# sch_USB3_0.net
KiCad netlist of a schematic drawn in Altium Designer
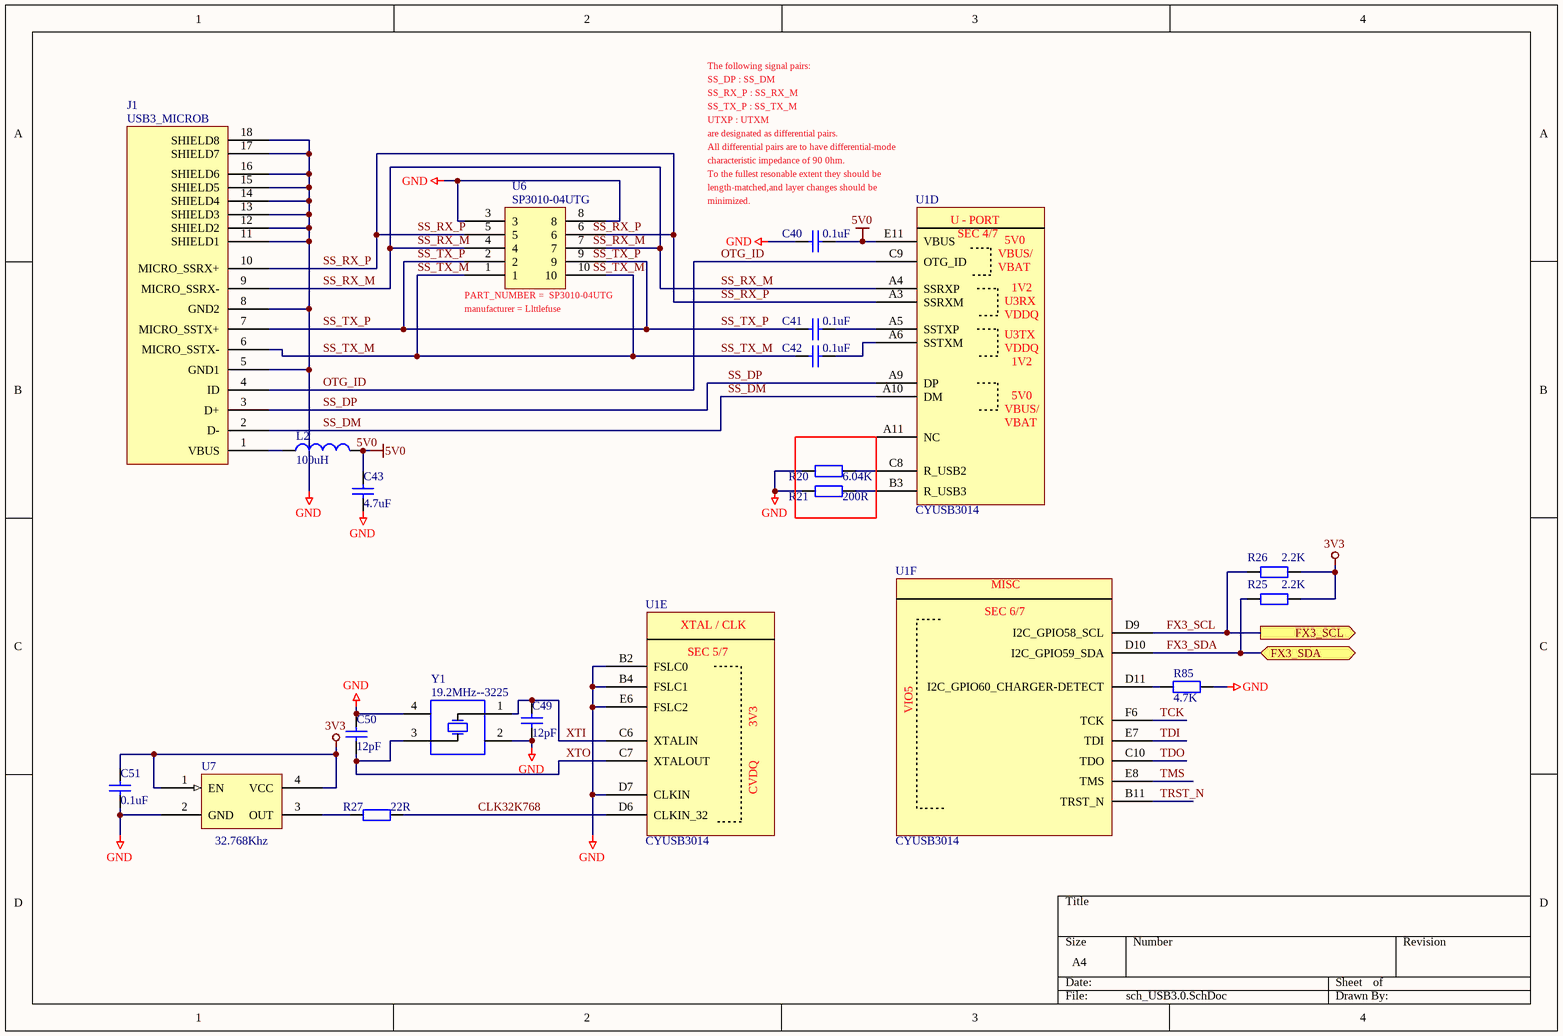
[diagram p0: sch_USB3.0.SchDoc]

(export (version "E")
  (design (tool "Eeschema 10.0.6"))
  (components
    (comp (ref "C40")
      (value "0.1uF")
      (footprint "0402C")
      (description "Capacitor")
      (fields (field (name "PUBLISHER") "Altium Limited"))
      (libsource (lib "Miscellaneous Devices") (part "Cap"))
    )
    (comp (ref "C41")
      (value "0.1uF")
      (footprint "0402C")
      (description "Capacitor")
      (fields (field (name "PUBLISHER") "Altium Limited"))
      (libsource (lib "Miscellaneous Devices") (part "Cap"))
    )
    (comp (ref "C42")
      (value "0.1uF")
      (footprint "0402C")
      (description "Capacitor")
      (fields (field (name "PUBLISHER") "Altium Limited"))
      (libsource (lib "Miscellaneous Devices") (part "Cap"))
    )
    (comp (ref "C43")
      (value "4.7uF")
      (description "Capacitor")
      (fields (field (name "PUBLISHER") "Altium Limited"))
      (libsource (lib "Miscellaneous Devices") (part "Cap"))
    )
    (comp (ref "C49")
      (value "12pF")
      (footprint "0402C")
      (description "Capacitor")
      (fields (field (name "PUBLISHER") "Altium Limited"))
      (libsource (lib "Miscellaneous Devices") (part "Cap"))
    )
    (comp (ref "C50")
      (value "12pF")
      (footprint "0402C")
      (description "Capacitor")
      (fields (field (name "PUBLISHER") "Altium Limited"))
      (libsource (lib "Miscellaneous Devices") (part "Cap"))
    )
    (comp (ref "C51")
      (value "0.1uF")
      (footprint "0402C")
      (description "Capacitor")
      (fields (field (name "PUBLISHER") "Altium Limited"))
      (libsource (lib "Miscellaneous Devices") (part "Cap"))
    )
    (comp (ref "J1")
      (value "USB3_MICROB")
      (footprint "USB3_BA_P65L130W51H28")
      (libsource (lib "SZG") (part "USB3_MICROB"))
    )
    (comp (ref "L2")
      (value "100uH")
      (description "Inductor")
      (libsource (lib "SWUST_ROBOT") (part "Inductor"))
    )
    (comp (ref "R20")
      (value "6.04K")
      (footprint "0402R")
      (description "Resistor")
      (fields (field (name "PUBLISHER") "Altium Limited"))
      (libsource (lib "SZG") (part "Resistor"))
    )
    (comp (ref "R21")
      (value "200R")
      (footprint "0402R")
      (description "Resistor")
      (fields (field (name "PUBLISHER") "Altium Limited"))
      (libsource (lib "SZG") (part "Resistor"))
    )
    (comp (ref "R25")
      (value "2.2K")
      (footprint "0402R")
      (description "Resistor")
      (fields (field (name "PUBLISHER") "Altium Limited"))
      (libsource (lib "SZG") (part "Resistor"))
    )
    (comp (ref "R26")
      (value "2.2K")
      (footprint "0402R")
      (description "Resistor")
      (fields (field (name "PUBLISHER") "Altium Limited"))
      (libsource (lib "SZG") (part "Resistor"))
    )
    (comp (ref "R27")
      (value "22R")
      (footprint "0402R")
      (description "Resistor")
      (fields (field (name "PUBLISHER") "Altium Limited"))
      (libsource (lib "SZG") (part "Resistor"))
    )
    (comp (ref "R85")
      (value "4.7K")
      (footprint "0402R")
      (description "Resistor")
      (fields (field (name "PUBLISHER") "Altium Limited"))
      (libsource (lib "SZG") (part "Resistor"))
    )
    (comp (ref "U1")
      (value "CYUSB3014")
      (footprint "FBGA121_P80L100W100H11")
      (libsource (lib "TXW") (part "CYUSB3014"))
    )
    (comp (ref "U6")
      (value "SP3010-04UTG")
      (footprint "UDFN10_SON_P50L25W10H55")
      (libsource (lib "SZG") (part "SP3010-04UTG"))
    )
    (comp (ref "U7")
      (value "XTAL-3225")
      (footprint "XTAL_3225")
      (libsource (lib "常用晶振器件图SCH") (part "XTAL."))
    )
    (comp (ref "Y1")
      (value "19.2MHz--3225")
      (footprint "XTAL_3225")
      (description "Crystal Oscillator")
      (libsource (lib "常用晶振器件图SCH") (part "XTAL"))
    )
  )
  (nets
    (net (code "1") (name "/CLK32K768") (class "Default")
      (node (ref "R27") (pin "1") (pinfunction "1_1") (pintype "passive"))
      (node (ref "U1") (pin "D6") (pinfunction "CLKIN_32_D6") (pintype "passive"))
    )
    (net (code "2") (name "/FX3_SCL") (class "Default")
      (node (ref "R26") (pin "2") (pinfunction "2_2") (pintype "passive"))
      (node (ref "U1") (pin "D9") (pinfunction "I2C_GPIO58_SCL_D9") (pintype "passive"))
    )
    (net (code "3") (name "/FX3_SDA") (class "Default")
      (node (ref "R25") (pin "2") (pinfunction "2_2") (pintype "passive"))
      (node (ref "U1") (pin "D10") (pinfunction "I2C_GPIO59_SDA_D10") (pintype "passive"))
    )
    (net (code "4") (name "/OTG_ID") (class "Default")
      (node (ref "J1") (pin "4") (pinfunction "ID_4") (pintype "power_in"))
      (node (ref "U1") (pin "C9") (pinfunction "OTG_ID_C9") (pintype "power_in"))
    )
    (net (code "5") (name "/SS_DM") (class "Default")
      (node (ref "J1") (pin "2") (pinfunction "D-_2") (pintype "power_in"))
      (node (ref "U1") (pin "A10") (pinfunction "DM_A10") (pintype "power_in"))
    )
    (net (code "6") (name "/SS_DP") (class "Default")
      (node (ref "J1") (pin "3") (pinfunction "D+_3") (pintype "power_in"))
      (node (ref "U1") (pin "A9") (pinfunction "DP_A9") (pintype "power_in"))
    )
    (net (code "7") (name "/SS_RX_M") (class "Default")
      (node (ref "J1") (pin "9") (pinfunction "MICRO_SSRX-_9") (pintype "power_in"))
      (node (ref "U1") (pin "A4") (pinfunction "SSRXP_A4") (pintype "power_in"))
      (node (ref "U6") (pin "4") (pinfunction "4_4") (pintype "passive"))
      (node (ref "U6") (pin "7") (pinfunction "7_7") (pintype "passive"))
    )
    (net (code "8") (name "/SS_RX_P") (class "Default")
      (node (ref "J1") (pin "10") (pinfunction "MICRO_SSRX+_10") (pintype "power_in"))
      (node (ref "U1") (pin "A3") (pinfunction "SSRXM_A3") (pintype "power_in"))
      (node (ref "U6") (pin "5") (pinfunction "5_5") (pintype "passive"))
      (node (ref "U6") (pin "6") (pinfunction "6_6") (pintype "passive"))
    )
    (net (code "9") (name "/SS_TX_M") (class "Default")
      (node (ref "C42") (pin "2") (pinfunction "2_2") (pintype "passive"))
      (node (ref "J1") (pin "6") (pinfunction "MICRO_SSTX-_6") (pintype "power_in"))
      (node (ref "U6") (pin "1") (pinfunction "1_1") (pintype "passive"))
      (node (ref "U6") (pin "10") (pinfunction "10_10") (pintype "passive"))
    )
    (net (code "10") (name "/SS_TX_P") (class "Default")
      (node (ref "C41") (pin "2") (pinfunction "2_2") (pintype "passive"))
      (node (ref "J1") (pin "7") (pinfunction "MICRO_SSTX+_7") (pintype "power_in"))
      (node (ref "U6") (pin "2") (pinfunction "2_2") (pintype "passive"))
      (node (ref "U6") (pin "9") (pinfunction "9_9") (pintype "passive"))
    )
    (net (code "11") (name "/TCK") (class "Default")
      (node (ref "U1") (pin "F6") (pinfunction "TCK_F6") (pintype "passive"))
    )
    (net (code "12") (name "/TDI") (class "Default")
      (node (ref "U1") (pin "E7") (pinfunction "TDI_E7") (pintype "passive"))
    )
    (net (code "13") (name "/TDO") (class "Default")
      (node (ref "U1") (pin "C10") (pinfunction "TDO_C10") (pintype "passive"))
    )
    (net (code "14") (name "/TMS") (class "Default")
      (node (ref "U1") (pin "E8") (pinfunction "TMS_E8") (pintype "passive"))
    )
    (net (code "15") (name "/TRST_N") (class "Default")
      (node (ref "U1") (pin "B11") (pinfunction "TRST_N_B11") (pintype "passive"))
    )
    (net (code "16") (name "/XTI") (class "Default")
      (node (ref "C49") (pin "2") (pinfunction "2_2") (pintype "passive"))
      (node (ref "U1") (pin "C6") (pinfunction "XTALIN_C6") (pintype "passive"))
      (node (ref "Y1") (pin "1") (pinfunction "1_1") (pintype "passive"))
    )
    (net (code "17") (name "/XTO") (class "Default")
      (node (ref "C50") (pin "1") (pinfunction "1_1") (pintype "passive"))
      (node (ref "U1") (pin "C7") (pinfunction "XTALOUT_C7") (pintype "passive"))
      (node (ref "Y1") (pin "3") (pinfunction "3_3") (pintype "passive"))
    )
    (net (code "18") (name "3V3") (class "Default")
      (node (ref "C51") (pin "2") (pinfunction "2_2") (pintype "passive"))
      (node (ref "R25") (pin "1") (pinfunction "1_1") (pintype "passive"))
      (node (ref "R26") (pin "1") (pinfunction "1_1") (pintype "passive"))
      (node (ref "U7") (pin "1") (pinfunction "EN_1") (pintype "input"))
      (node (ref "U7") (pin "4") (pinfunction "VCC_4") (pintype "passive"))
    )
    (net (code "19") (name "5V0") (class "Default")
      (node (ref "C40") (pin "1") (pinfunction "1_1") (pintype "passive"))
      (node (ref "C43") (pin "2") (pinfunction "2_2") (pintype "passive"))
      (node (ref "L2") (pin "2") (pinfunction "2_2") (pintype "passive"))
      (node (ref "U1") (pin "E11") (pinfunction "VBUS_E11") (pintype "power_in"))
    )
    (net (code "20") (name "GND") (class "Default")
      (node (ref "C40") (pin "2") (pinfunction "2_2") (pintype "passive"))
      (node (ref "C43") (pin "1") (pinfunction "1_1") (pintype "passive"))
      (node (ref "C49") (pin "1") (pinfunction "1_1") (pintype "passive"))
      (node (ref "C50") (pin "2") (pinfunction "2_2") (pintype "passive"))
      (node (ref "C51") (pin "1") (pinfunction "1_1") (pintype "passive"))
      (node (ref "J1") (pin "11") (pinfunction "SHIELD1_11") (pintype "power_in"))
      (node (ref "J1") (pin "12") (pinfunction "SHIELD2_12") (pintype "power_in"))
      (node (ref "J1") (pin "13") (pinfunction "SHIELD3_13") (pintype "power_in"))
      (node (ref "J1") (pin "14") (pinfunction "SHIELD4_14") (pintype "power_in"))
      (node (ref "J1") (pin "15") (pinfunction "SHIELD5_15") (pintype "power_in"))
      (node (ref "J1") (pin "16") (pinfunction "SHIELD6_16") (pintype "power_in"))
      (node (ref "J1") (pin "17") (pinfunction "SHIELD7_17") (pintype "power_in"))
      (node (ref "J1") (pin "18") (pinfunction "SHIELD8_18") (pintype "power_in"))
      (node (ref "J1") (pin "5") (pinfunction "GND1_5") (pintype "power_in"))
      (node (ref "J1") (pin "8") (pinfunction "GND2_8") (pintype "power_in"))
      (node (ref "R20") (pin "2") (pinfunction "2_2") (pintype "passive"))
      (node (ref "R21") (pin "2") (pinfunction "2_2") (pintype "passive"))
      (node (ref "R85") (pin "1") (pinfunction "1_1") (pintype "passive"))
      (node (ref "U1") (pin "B2") (pinfunction "FSLC0_B2") (pintype "passive"))
      (node (ref "U1") (pin "B4") (pinfunction "FSLC1_B4") (pintype "passive"))
      (node (ref "U1") (pin "D7") (pinfunction "CLKIN_D7") (pintype "passive"))
      (node (ref "U1") (pin "E6") (pinfunction "FSLC2_E6") (pintype "passive"))
      (node (ref "U6") (pin "3") (pinfunction "3_3") (pintype "passive"))
      (node (ref "U6") (pin "8") (pinfunction "8_8") (pintype "passive"))
      (node (ref "U7") (pin "2") (pinfunction "GND_2") (pintype "passive"))
      (node (ref "Y1") (pin "2") (pinfunction "2_2") (pintype "passive"))
      (node (ref "Y1") (pin "4") (pinfunction "4_4") (pintype "passive"))
    )
    (net (code "21") (name "Net-(J1-VBUS)") (class "Default")
      (node (ref "J1") (pin "1") (pinfunction "VBUS_1") (pintype "power_in"))
      (node (ref "L2") (pin "1") (pinfunction "1_1") (pintype "passive"))
    )
    (net (code "22") (name "Net-(U1D-R_USB2)") (class "Default")
      (node (ref "R20") (pin "1") (pinfunction "1_1") (pintype "passive"))
      (node (ref "U1") (pin "C8") (pinfunction "R_USB2_C8") (pintype "power_in"))
    )
    (net (code "23") (name "Net-(U1D-R_USB3)") (class "Default")
      (node (ref "R21") (pin "1") (pinfunction "1_1") (pintype "passive"))
      (node (ref "U1") (pin "B3") (pinfunction "R_USB3_B3") (pintype "power_in"))
    )
    (net (code "24") (name "Net-(U1D-SSTXM)") (class "Default")
      (node (ref "C42") (pin "1") (pinfunction "1_1") (pintype "passive"))
      (node (ref "U1") (pin "A6") (pinfunction "SSTXM_A6") (pintype "power_in"))
    )
    (net (code "25") (name "Net-(U1D-SSTXP)") (class "Default")
      (node (ref "C41") (pin "1") (pinfunction "1_1") (pintype "passive"))
      (node (ref "U1") (pin "A5") (pinfunction "SSTXP_A5") (pintype "power_in"))
    )
    (net (code "26") (name "Net-(U1F-I2C_GPIO60_CHARGER-DETECT)") (class "Default")
      (node (ref "R85") (pin "2") (pinfunction "2_2") (pintype "passive"))
      (node (ref "U1") (pin "D11") (pinfunction "I2C_GPIO60_CHARGER-DETECT_D11") (pintype "passive"))
    )
    (net (code "27") (name "Net-(U7-OUT)") (class "Default")
      (node (ref "R27") (pin "2") (pinfunction "2_2") (pintype "passive"))
      (node (ref "U7") (pin "3") (pinfunction "OUT_3") (pintype "passive"))
    )
    (net (code "28") (name "unconnected-(U1D-NC-PadA11)") (class "Default")
      (node (ref "U1") (pin "A11") (pinfunction "NC_A11") (pintype "power_in"))
    )
  )
)
